# adc_buffer.net
KiCad netlist of a schematic drawn in Altium Designer
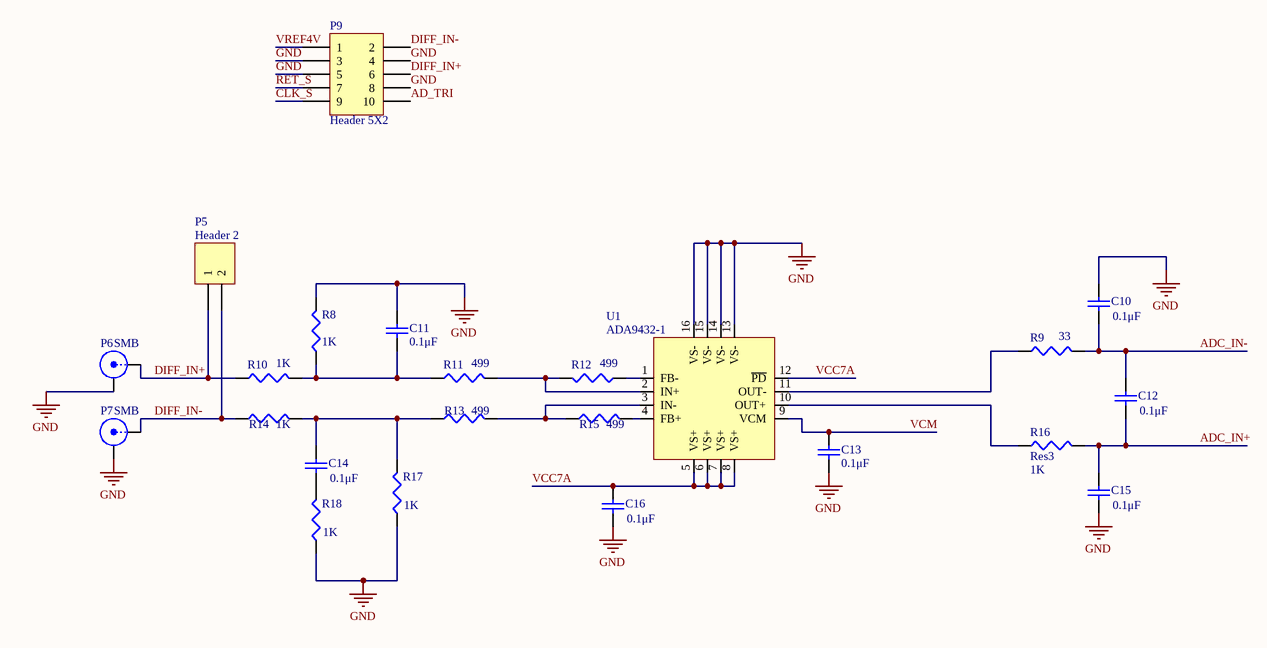
[diagram p0: adc_buffer.SchDoc]

(export (version "E")
  (design (tool "Eeschema 10.0.6"))
  (components
    (comp (ref "C10")
      (value "0.1μF")
      (footprint "1608[0603]")
      (description "Capacitor (Semiconductor SIM Model)")
      (fields (field (name "Comment") "Cap Semi") (field (name "PUBLISHER") "Altium Limited"))
      (libsource (lib "Miscellaneous Devices") (part "Cap Semi"))
    )
    (comp (ref "C11")
      (value "0.1μF")
      (footprint "1608[0603]")
      (description "Capacitor (Semiconductor SIM Model)")
      (fields (field (name "Comment") "Cap Semi") (field (name "PUBLISHER") "Altium Limited"))
      (libsource (lib "Miscellaneous Devices") (part "Cap Semi"))
    )
    (comp (ref "C12")
      (value "0.1μF")
      (footprint "1608[0603]")
      (description "Capacitor (Semiconductor SIM Model)")
      (fields (field (name "Comment") "Cap Semi") (field (name "PUBLISHER") "Altium Limited"))
      (libsource (lib "Miscellaneous Devices") (part "Cap Semi"))
    )
    (comp (ref "C13")
      (value "0.1μF")
      (footprint "1608[0603]")
      (description "Capacitor (Semiconductor SIM Model)")
      (fields (field (name "Comment") "Cap Semi") (field (name "PUBLISHER") "Altium Limited"))
      (libsource (lib "Miscellaneous Devices") (part "Cap Semi"))
    )
    (comp (ref "C14")
      (value "0.1μF")
      (footprint "1608[0603]")
      (description "Capacitor (Semiconductor SIM Model)")
      (fields (field (name "Comment") "Cap Semi") (field (name "PUBLISHER") "Altium Limited"))
      (libsource (lib "Miscellaneous Devices") (part "Cap Semi"))
    )
    (comp (ref "C15")
      (value "0.1μF")
      (footprint "1608[0603]")
      (description "Capacitor (Semiconductor SIM Model)")
      (fields (field (name "Comment") "Cap Semi") (field (name "PUBLISHER") "Altium Limited"))
      (libsource (lib "Miscellaneous Devices") (part "Cap Semi"))
    )
    (comp (ref "C16")
      (value "0.1μF")
      (footprint "1608[0603]")
      (description "Capacitor (Semiconductor SIM Model)")
      (fields (field (name "Comment") "Cap Semi") (field (name "PUBLISHER") "Altium Limited"))
      (libsource (lib "Miscellaneous Devices") (part "Cap Semi"))
    )
    (comp (ref "P5")
      (value "Header 2")
      (footprint "HDR1X2")
      (description "Header, 2-Pin")
      (fields (field (name "PUBLISHER") "Altium Limited"))
      (libsource (lib "Miscellaneous Connectors") (part "Header 2"))
    )
    (comp (ref "P6")
      (value "SMB")
      (footprint "SMB_V-RJ45")
      (description "SMB Straight Connector")
      (fields (field (name "PUBLISHER") "Altium Limited"))
      (libsource (lib "Miscellaneous Connectors") (part "SMB"))
    )
    (comp (ref "P7")
      (value "SMB")
      (footprint "SMB_V-RJ45")
      (description "SMB Straight Connector")
      (fields (field (name "PUBLISHER") "Altium Limited"))
      (libsource (lib "Miscellaneous Connectors") (part "SMB"))
    )
    (comp (ref "P9")
      (value "Header 5X2")
      (footprint "HDR2X5")
      (description "Header, 5-Pin, Dual row")
      (fields (field (name "PUBLISHER") "Altium Limited"))
      (libsource (lib "Miscellaneous Connectors") (part "Header 5X2"))
    )
    (comp (ref "R8")
      (value "1K")
      (footprint "J1-0603")
      (description "Resistor")
      (fields (field (name "Comment") "Res3") (field (name "PUBLISHER") "Altium Limited"))
      (libsource (lib "Miscellaneous Devices") (part "Res3"))
    )
    (comp (ref "R9")
      (value "33")
      (footprint "J1-0603")
      (description "Resistor")
      (fields (field (name "Comment") "Res3") (field (name "PUBLISHER") "Altium Limited"))
      (libsource (lib "Miscellaneous Devices") (part "Res3"))
    )
    (comp (ref "R10")
      (value "1K")
      (footprint "J1-0603")
      (description "Resistor")
      (fields (field (name "Comment") "Res3") (field (name "PUBLISHER") "Altium Limited"))
      (libsource (lib "Miscellaneous Devices") (part "Res3"))
    )
    (comp (ref "R11")
      (value "499")
      (footprint "J1-0603")
      (description "Resistor")
      (fields (field (name "Comment") "Res3") (field (name "PUBLISHER") "Altium Limited"))
      (libsource (lib "Miscellaneous Devices") (part "Res3"))
    )
    (comp (ref "R12")
      (value "499")
      (footprint "J1-0603")
      (description "Resistor")
      (fields (field (name "Comment") "Res3") (field (name "PUBLISHER") "Altium Limited"))
      (libsource (lib "Miscellaneous Devices") (part "Res3"))
    )
    (comp (ref "R13")
      (value "499")
      (footprint "J1-0603")
      (description "Resistor")
      (fields (field (name "Comment") "Res3") (field (name "PUBLISHER") "Altium Limited"))
      (libsource (lib "Miscellaneous Devices") (part "Res3"))
    )
    (comp (ref "R14")
      (value "1K")
      (footprint "J1-0603")
      (description "Resistor")
      (fields (field (name "Comment") "Res3") (field (name "PUBLISHER") "Altium Limited"))
      (libsource (lib "Miscellaneous Devices") (part "Res3"))
    )
    (comp (ref "R15")
      (value "499")
      (footprint "J1-0603")
      (description "Resistor")
      (fields (field (name "Comment") "Res3") (field (name "PUBLISHER") "Altium Limited"))
      (libsource (lib "Miscellaneous Devices") (part "Res3"))
    )
    (comp (ref "R16")
      (value "Res3")
      (footprint "J1-0603")
      (description "Resistor")
      (fields (field (name "ALTIUM_VALUE") "1K") (field (name "PUBLISHER") "Altium Limited"))
      (libsource (lib "Miscellaneous Devices") (part "Res3"))
    )
    (comp (ref "R17")
      (value "1K")
      (footprint "J1-0603")
      (description "Resistor")
      (fields (field (name "Comment") "Res3") (field (name "PUBLISHER") "Altium Limited"))
      (libsource (lib "Miscellaneous Devices") (part "Res3"))
    )
    (comp (ref "R18")
      (value "1K")
      (footprint "J1-0603")
      (description "Resistor")
      (fields (field (name "Comment") "Res3") (field (name "PUBLISHER") "Altium Limited"))
      (libsource (lib "Miscellaneous Devices") (part "Res3"))
    )
    (comp (ref "U1")
      (value "ADA9432-1")
      (footprint "QFN50P300X300X100VQ-17N")
      (libsource (lib "nir_usb") (part "ADA9432-1"))
    )
  )
  (nets
    (net (code "1") (name "/ADC_IN+") (class "Default")
      (node (ref "C12") (pin "1") (pinfunction "1_1") (pintype "passive"))
      (node (ref "C15") (pin "2") (pinfunction "2_2") (pintype "passive"))
      (node (ref "R16") (pin "2") (pinfunction "2_2") (pintype "passive"))
    )
    (net (code "2") (name "/ADC_IN-") (class "Default")
      (node (ref "C10") (pin "1") (pinfunction "1_1") (pintype "passive"))
      (node (ref "C12") (pin "2") (pinfunction "2_2") (pintype "passive"))
      (node (ref "R9") (pin "2") (pinfunction "2_2") (pintype "passive"))
    )
    (net (code "3") (name "/AD_TRI") (class "Default")
      (node (ref "P9") (pin "10") (pinfunction "10_10") (pintype "passive"))
    )
    (net (code "4") (name "/CLK_S") (class "Default")
      (node (ref "P9") (pin "9") (pinfunction "9_9") (pintype "passive"))
    )
    (net (code "5") (name "/DIFF_IN+") (class "Default")
      (node (ref "P5") (pin "1") (pinfunction "1_1") (pintype "passive"))
      (node (ref "P6") (pin "1") (pinfunction "X_1") (pintype "passive"))
      (node (ref "P9") (pin "6") (pinfunction "6_6") (pintype "passive"))
      (node (ref "R10") (pin "1") (pinfunction "1_1") (pintype "passive"))
    )
    (net (code "6") (name "/DIFF_IN-") (class "Default")
      (node (ref "P5") (pin "2") (pinfunction "2_2") (pintype "passive"))
      (node (ref "P7") (pin "1") (pinfunction "X_1") (pintype "passive"))
      (node (ref "P9") (pin "2") (pinfunction "2_2") (pintype "passive"))
      (node (ref "R14") (pin "1") (pinfunction "1_1") (pintype "passive"))
    )
    (net (code "7") (name "/RET_S") (class "Default")
      (node (ref "P9") (pin "7") (pinfunction "7_7") (pintype "passive"))
    )
    (net (code "8") (name "/VCC7A") (class "Default")
      (node (ref "C16") (pin "2") (pinfunction "2_2") (pintype "passive"))
      (node (ref "U1") (pin "12") (pinfunction "~{PD}_12") (pintype "passive"))
      (node (ref "U1") (pin "5") (pinfunction "VS+_5") (pintype "passive"))
      (node (ref "U1") (pin "6") (pinfunction "VS+_6") (pintype "passive"))
      (node (ref "U1") (pin "7") (pinfunction "VS+_7") (pintype "passive"))
      (node (ref "U1") (pin "8") (pinfunction "VS+_8") (pintype "passive"))
    )
    (net (code "9") (name "/VCM") (class "Default")
      (node (ref "C13") (pin "2") (pinfunction "2_2") (pintype "passive"))
      (node (ref "U1") (pin "9") (pinfunction "VCM_9") (pintype "passive"))
    )
    (net (code "10") (name "/VREF4V") (class "Default")
      (node (ref "P9") (pin "1") (pinfunction "1_1") (pintype "passive"))
    )
    (net (code "11") (name "GND") (class "Default")
      (node (ref "C10") (pin "2") (pinfunction "2_2") (pintype "passive"))
      (node (ref "C11") (pin "2") (pinfunction "2_2") (pintype "passive"))
      (node (ref "C13") (pin "1") (pinfunction "1_1") (pintype "passive"))
      (node (ref "C15") (pin "1") (pinfunction "1_1") (pintype "passive"))
      (node (ref "C16") (pin "1") (pinfunction "1_1") (pintype "passive"))
      (node (ref "P6") (pin "2") (pinfunction "Y_2") (pintype "passive"))
      (node (ref "P7") (pin "2") (pinfunction "Y_2") (pintype "passive"))
      (node (ref "P9") (pin "3") (pinfunction "3_3") (pintype "passive"))
      (node (ref "P9") (pin "4") (pinfunction "4_4") (pintype "passive"))
      (node (ref "P9") (pin "5") (pinfunction "5_5") (pintype "passive"))
      (node (ref "P9") (pin "8") (pinfunction "8_8") (pintype "passive"))
      (node (ref "R17") (pin "1") (pinfunction "1_1") (pintype "passive"))
      (node (ref "R18") (pin "1") (pinfunction "1_1") (pintype "passive"))
      (node (ref "R8") (pin "2") (pinfunction "2_2") (pintype "passive"))
      (node (ref "U1") (pin "13") (pinfunction "VS-_13") (pintype "passive"))
      (node (ref "U1") (pin "14") (pinfunction "VS-_14") (pintype "passive"))
      (node (ref "U1") (pin "15") (pinfunction "VS-_15") (pintype "passive"))
      (node (ref "U1") (pin "16") (pinfunction "VS-_16") (pintype "passive"))
    )
    (net (code "12") (name "Net-(C11-Pad1)") (class "Default")
      (node (ref "C11") (pin "1") (pinfunction "1_1") (pintype "passive"))
      (node (ref "R10") (pin "2") (pinfunction "2_2") (pintype "passive"))
      (node (ref "R11") (pin "1") (pinfunction "1_1") (pintype "passive"))
      (node (ref "R8") (pin "1") (pinfunction "1_1") (pintype "passive"))
    )
    (net (code "13") (name "Net-(C14-Pad1)") (class "Default")
      (node (ref "C14") (pin "1") (pinfunction "1_1") (pintype "passive"))
      (node (ref "R18") (pin "2") (pinfunction "2_2") (pintype "passive"))
    )
    (net (code "14") (name "Net-(C14-Pad2)") (class "Default")
      (node (ref "C14") (pin "2") (pinfunction "2_2") (pintype "passive"))
      (node (ref "R13") (pin "1") (pinfunction "1_1") (pintype "passive"))
      (node (ref "R14") (pin "2") (pinfunction "2_2") (pintype "passive"))
      (node (ref "R17") (pin "2") (pinfunction "2_2") (pintype "passive"))
    )
    (net (code "15") (name "Net-(U1-FB+)") (class "Default")
      (node (ref "R15") (pin "2") (pinfunction "2_2") (pintype "passive"))
      (node (ref "U1") (pin "4") (pinfunction "FB+_4") (pintype "passive"))
    )
    (net (code "16") (name "Net-(U1-FB-)") (class "Default")
      (node (ref "R12") (pin "1") (pinfunction "1_1") (pintype "passive"))
      (node (ref "U1") (pin "1") (pinfunction "FB-_1") (pintype "passive"))
    )
    (net (code "17") (name "Net-(U1-IN+)") (class "Default")
      (node (ref "R11") (pin "2") (pinfunction "2_2") (pintype "passive"))
      (node (ref "R12") (pin "2") (pinfunction "2_2") (pintype "passive"))
      (node (ref "U1") (pin "2") (pinfunction "IN+_2") (pintype "passive"))
    )
    (net (code "18") (name "Net-(U1-IN-)") (class "Default")
      (node (ref "R13") (pin "2") (pinfunction "2_2") (pintype "passive"))
      (node (ref "R15") (pin "1") (pinfunction "1_1") (pintype "passive"))
      (node (ref "U1") (pin "3") (pinfunction "IN-_3") (pintype "passive"))
    )
    (net (code "19") (name "Net-(U1-OUT+)") (class "Default")
      (node (ref "R16") (pin "1") (pinfunction "1_1") (pintype "passive"))
      (node (ref "U1") (pin "10") (pinfunction "OUT+_10") (pintype "passive"))
    )
    (net (code "20") (name "Net-(U1-OUT-)") (class "Default")
      (node (ref "R9") (pin "1") (pinfunction "1_1") (pintype "passive"))
      (node (ref "U1") (pin "11") (pinfunction "OUT-_11") (pintype "passive"))
    )
  )
)
